# motherboard_2ch_arduino.net
KiCad netlist of a schematic drawn in Altium Designer
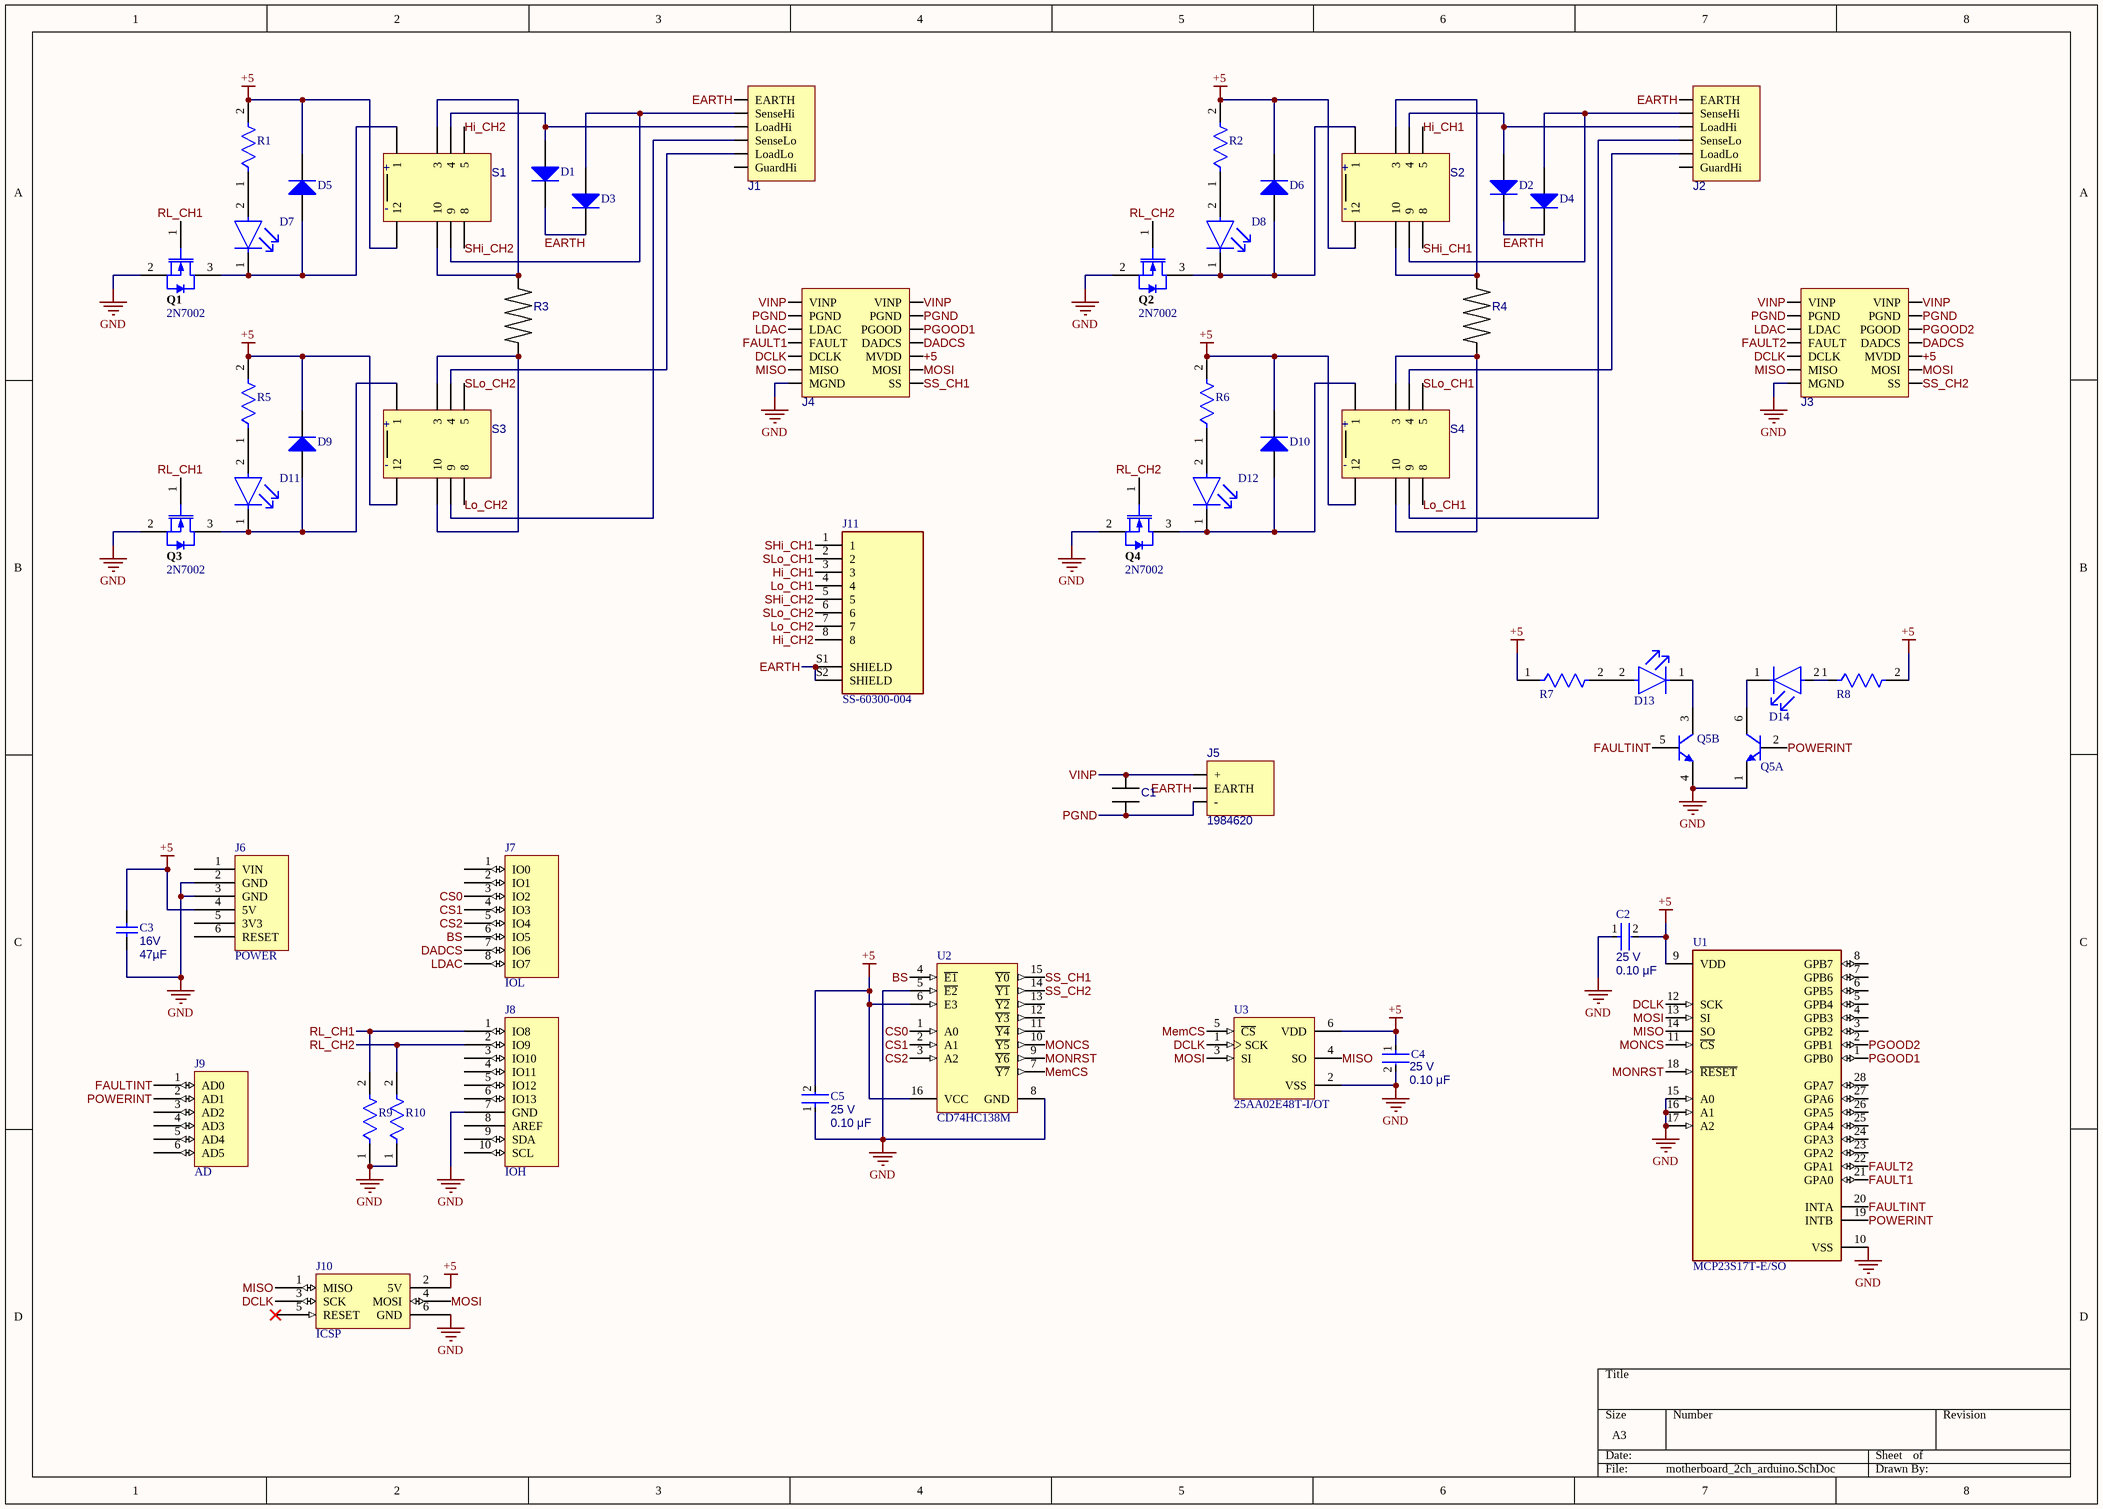
[diagram p0: motherboard_2ch_arduino.SchDoc]

(export (version "E")
  (design (tool "Eeschema 10.0.6"))
  (components
    (comp (ref "C1")
      (value "KRM55TR71H226MH01L")
      (footprint "CAPC6050X50M")
      (libsource (lib "manual") (part "CAP22uF"))
    )
    (comp (ref "C2")
      (value "0.10 μF")
      (footprint "FP-C1206C-EB-IPC_A")
      (description "CAP CER 0.1UF 25V C0G/NP0 1206")
      (fields
        (field (name "VOLTAGE RATING") "25 V")
        (field (name "MANUFACTURER") "KEMET")
        (field (name "TOLERANCE") "0.05")
      )
      (libsource (lib "Altium Content Vault") (part "b4654b650e69147ec39a6b967a45e02"))
    )
    (comp (ref "C3")
      (value "1210YD107MAT2A")
      (footprint "MURA-1210_H_2.7_M")
      (description "Cap Ceramic, 47 uF, +/- 10%, -55 to 85 degC, 2-Pin SMD (1210), RoHS, Tape and Reel")
      (fields
        (field (name "VOLTAGE RATING DC") "16V")
        (field (name "CAPACITANCE") "47µF")
        (field (name "TOLERANCE") "±10%")
        (field (name "MANUFACTURER") "Murata")
      )
      (libsource (lib "Altium Content Vault") (part "CAP-NP-2"))
    )
    (comp (ref "C4")
      (value "0.10 μF")
      (footprint "FP-C1206C-EB-IPC_A")
      (description "CAP CER 0.1UF 25V C0G/NP0 1206")
      (fields
        (field (name "VOLTAGE RATING") "25 V")
        (field (name "MANUFACTURER") "KEMET")
        (field (name "TOLERANCE") "0.05")
      )
      (libsource (lib "Altium Content Vault") (part "b4654b650e69147ec39a6b967a45e02"))
    )
    (comp (ref "C5")
      (value "0.10 μF")
      (footprint "FP-C1206C-EB-IPC_A")
      (description "CAP CER 0.1UF 25V C0G/NP0 1206")
      (fields
        (field (name "VOLTAGE RATING") "25 V")
        (field (name "MANUFACTURER") "KEMET")
        (field (name "TOLERANCE") "0.05")
      )
      (libsource (lib "Altium Content Vault") (part "b4654b650e69147ec39a6b967a45e02"))
    )
    (comp (ref "D1")
      (value "SMAJ33CA-TR")
      (footprint "STM-SMA-2_V")
      (description "Transil(TM) Diode, 33 A, 36.7 V, -55 to 150 degC, 2-Pin SMA, RoHS, Tape and Reel")
      (fields (field (name "MANUFACTURER") "STMicroelectronics"))
      (libsource (lib "Altium Content Vault") (part "D-AK-2"))
    )
    (comp (ref "D2")
      (value "SMAJ33CA-TR")
      (footprint "STM-SMA-2_V")
      (description "Transil(TM) Diode, 33 A, 36.7 V, -55 to 150 degC, 2-Pin SMA, RoHS, Tape and Reel")
      (fields (field (name "MANUFACTURER") "STMicroelectronics"))
      (libsource (lib "Altium Content Vault") (part "D-AK-2"))
    )
    (comp (ref "D3")
      (value "SMAJ33CA-TR")
      (footprint "STM-SMA-2_V")
      (description "Transil(TM) Diode, 33 A, 36.7 V, -55 to 150 degC, 2-Pin SMA, RoHS, Tape and Reel")
      (fields (field (name "MANUFACTURER") "STMicroelectronics"))
      (libsource (lib "Altium Content Vault") (part "D-AK-2"))
    )
    (comp (ref "D4")
      (value "SMAJ33CA-TR")
      (footprint "STM-SMA-2_V")
      (description "Transil(TM) Diode, 33 A, 36.7 V, -55 to 150 degC, 2-Pin SMA, RoHS, Tape and Reel")
      (fields (field (name "MANUFACTURER") "STMicroelectronics"))
      (libsource (lib "Altium Content Vault") (part "D-AK-2"))
    )
    (comp (ref "D5")
      (value "1N4148W-7-F")
      (footprint "DIOD-SOD123-2_V")
      (description "Fast Switching Diode, 100 V, 0.15 A, -65 to 150 degC, 2-Pin?SOD123, RoHS, Tape and Reel")
      (fields (field (name "MANUFACTURER") "DiodesIncorporated"))
      (libsource (lib "Altium Content Vault") (part "D-AK-2"))
    )
    (comp (ref "D6")
      (value "1N4148W-7-F")
      (footprint "DIOD-SOD123-2_V")
      (description "Fast Switching Diode, 100 V, 0.15 A, -65 to 150 degC, 2-Pin?SOD123, RoHS, Tape and Reel")
      (fields (field (name "MANUFACTURER") "DiodesIncorporated"))
      (libsource (lib "Altium Content Vault") (part "D-AK-2"))
    )
    (comp (ref "D7")
      (value "LTST-C150KGKT")
      (footprint "FP-LTST-C150KGKT-MFG")
      (description "LED GREEN CLEAR 1206 SMD")
      (libsource (lib "Altium Content Vault") (part "8706943c75ba83719d021d2fdc84c58"))
    )
    (comp (ref "D8")
      (value "LTST-C150KGKT")
      (footprint "FP-LTST-C150KGKT-MFG")
      (description "LED GREEN CLEAR 1206 SMD")
      (libsource (lib "Altium Content Vault") (part "8706943c75ba83719d021d2fdc84c58"))
    )
    (comp (ref "D9")
      (value "1N4148W-7-F")
      (footprint "DIOD-SOD123-2_V")
      (description "Fast Switching Diode, 100 V, 0.15 A, -65 to 150 degC, 2-Pin?SOD123, RoHS, Tape and Reel")
      (fields (field (name "MANUFACTURER") "DiodesIncorporated"))
      (libsource (lib "Altium Content Vault") (part "D-AK-2"))
    )
    (comp (ref "D10")
      (value "1N4148W-7-F")
      (footprint "DIOD-SOD123-2_V")
      (description "Fast Switching Diode, 100 V, 0.15 A, -65 to 150 degC, 2-Pin?SOD123, RoHS, Tape and Reel")
      (fields (field (name "MANUFACTURER") "DiodesIncorporated"))
      (libsource (lib "Altium Content Vault") (part "D-AK-2"))
    )
    (comp (ref "D11")
      (value "LTST-C150KGKT")
      (footprint "FP-LTST-C150KGKT-MFG")
      (description "LED GREEN CLEAR 1206 SMD")
      (libsource (lib "Altium Content Vault") (part "8706943c75ba83719d021d2fdc84c58"))
    )
    (comp (ref "D12")
      (value "LTST-C150KGKT")
      (footprint "FP-LTST-C150KGKT-MFG")
      (description "LED GREEN CLEAR 1206 SMD")
      (libsource (lib "Altium Content Vault") (part "8706943c75ba83719d021d2fdc84c58"))
    )
    (comp (ref "D13")
      (value "LTST-C150KGKT")
      (footprint "FP-LTST-C150KGKT-MFG")
      (description "LED GREEN CLEAR 1206 SMD")
      (libsource (lib "Altium Content Vault") (part "8706943c75ba83719d021d2fdc84c58"))
    )
    (comp (ref "D14")
      (value "LTST-C150KGKT")
      (footprint "FP-LTST-C150KGKT-MFG")
      (description "LED GREEN CLEAR 1206 SMD")
      (libsource (lib "Altium Content Vault") (part "8706943c75ba83719d021d2fdc84c58"))
    )
    (comp (ref "J1") (value "5-146276-6") (footprint "SMUIO") (libsource (lib "manual") (part "SMUIO")))
    (comp (ref "J2") (value "5-146276-6") (footprint "SMUIO") (libsource (lib "manual") (part "SMUIO")))
    (comp (ref "J3") (value "5-146252-7") (footprint "DATAIO") (libsource (lib "manual") (part "DATAIO")))
    (comp (ref "J4") (value "5-146252-7") (footprint "DATAIO") (libsource (lib "manual") (part "DATAIO")))
    (comp (ref "J5") (value "1984620") (footprint "1984620") (libsource (lib "manual") (part "POWERJACK")))
    (comp (ref "J6") (value "POWER") (footprint "Header 6x1 8.5mm") (libsource (lib "Header") (part "POWER")))
    (comp (ref "J7") (value "IOL") (footprint "Header 8x1 8.5mm") (libsource (lib "Header") (part "IOL")))
    (comp (ref "J8") (value "IOH") (footprint "Header 10x1 8.5mm") (libsource (lib "Header") (part "IOH")))
    (comp (ref "J9")
      (value "AD")
      (footprint "Header:Header 6x1 8.5mm")
      (libsource (lib "Header") (part "AD"))
    )
    (comp (ref "J10") (value "ICSP") (footprint "ICSP") (libsource (lib "Header") (part "ICSP")))
    (comp (ref "J11")
      (value "SS-60300-004")
      (footprint "BEL_SS-60300-004")
      (description "Modular Jack ¦ CAT6a ¦ Horizontal (90) ¦ 8P 8C ¦ NF Shielded")
      (fields (field (name "MF") "Stewart Connector"))
      (libsource (lib "SS-60300-004") (part "SS-60300-004"))
    )
    (comp (ref "Q1")
      (value "2N7002")
      (footprint "INF-PG-SOT23_M")
      (fields (field (name "MANUFACTURER") "Infineon"))
      (libsource (lib "Altium Content Vault") (part "INF-NDMOS-GSD-3"))
    )
    (comp (ref "Q2")
      (value "2N7002")
      (footprint "INF-PG-SOT23_M")
      (fields (field (name "MANUFACTURER") "Infineon"))
      (libsource (lib "Altium Content Vault") (part "INF-NDMOS-GSD-3"))
    )
    (comp (ref "Q3")
      (value "2N7002")
      (footprint "INF-PG-SOT23_M")
      (fields (field (name "MANUFACTURER") "Infineon"))
      (libsource (lib "Altium Content Vault") (part "INF-NDMOS-GSD-3"))
    )
    (comp (ref "Q4")
      (value "2N7002")
      (footprint "INF-PG-SOT23_M")
      (fields (field (name "MANUFACTURER") "Infineon"))
      (libsource (lib "Altium Content Vault") (part "INF-NDMOS-GSD-3"))
    )
    (comp (ref "Q5")
      (value "MBT3904DW1T1G")
      (footprint "ONSC-SOT-363-6-419B-02_W_V")
      (description "Dual General Purpose Transistors, 6-Pin SOT-363, Pb-Free, Tape and Reel")
      (fields (field (name "MANUFACTURER") "On Semiconductor"))
      (libsource (lib "Altium Content Vault") (part "ONSC-NPN_NPN-6_F"))
    )
    (comp (ref "R1")
      (value "RN73R2BTTD1001B25")
      (footprint "FP-RC3216-IPC_A")
      (description "Res Thick Film 1206 1kΩ 5% 0.25W ±100ppm/°C Molded SMD T/R")
      (fields (field (name "TOLERANCE") "5%"))
      (libsource (lib "Altium Content Vault") (part "1029c3af85768c4190bb7ad29bc67b5"))
    )
    (comp (ref "R2")
      (value "RC3216J102CS")
      (footprint "FP-RC3216-IPC_A")
      (description "Res Thick Film 1206 1kΩ 5% 0.25W ±100ppm/°C Molded SMD T/R")
      (fields (field (name "TOLERANCE") "5%"))
      (libsource (lib "Altium Content Vault") (part "1029c3af85768c4190bb7ad29bc67b5"))
    )
    (comp (ref "R3")
      (value "Y1453500R000V9L")
      (footprint "Y1453500R000V9L")
      (libsource (lib "manual") (part "Y1453500R000V9L"))
    )
    (comp (ref "R4")
      (value "Y1453500R000V9L")
      (footprint "Y1453500R000V9L")
      (libsource (lib "manual") (part "Y1453500R000V9L"))
    )
    (comp (ref "R5")
      (value "RC3216J102CS")
      (footprint "FP-RC3216-IPC_A")
      (description "Res Thick Film 1206 1kΩ 5% 0.25W ±100ppm/°C Molded SMD T/R")
      (fields (field (name "TOLERANCE") "5%"))
      (libsource (lib "Altium Content Vault") (part "1029c3af85768c4190bb7ad29bc67b5"))
    )
    (comp (ref "R6")
      (value "RC3216J102CS")
      (footprint "FP-RC3216-IPC_A")
      (description "Res Thick Film 1206 1kΩ 5% 0.25W ±100ppm/°C Molded SMD T/R")
      (fields (field (name "TOLERANCE") "5%"))
      (libsource (lib "Altium Content Vault") (part "1029c3af85768c4190bb7ad29bc67b5"))
    )
    (comp (ref "R7")
      (value "RC3216J102CS")
      (footprint "FP-RC3216-IPC_A")
      (description "Res Thick Film 1206 1kΩ 5% 0.25W ±100ppm/°C Molded SMD T/R")
      (fields (field (name "TOLERANCE") "5%"))
      (libsource (lib "Altium Content Vault") (part "1029c3af85768c4190bb7ad29bc67b5"))
    )
    (comp (ref "R8")
      (value "RC3216J102CS")
      (footprint "FP-RC3216-IPC_A")
      (description "Res Thick Film 1206 1kΩ 5% 0.25W ±100ppm/°C Molded SMD T/R")
      (fields (field (name "TOLERANCE") "5%"))
      (libsource (lib "Altium Content Vault") (part "1029c3af85768c4190bb7ad29bc67b5"))
    )
    (comp (ref "R9")
      (value "RN73H2BTTD1002B10")
      (footprint "FP-RC3216-IPC_A")
      (description "RES SMD 10K OHM 1% 1/4W 1206")
      (fields (field (name "TOLERANCE") "1%"))
      (libsource (lib "Altium Content Vault") (part "1029c3af85768c4190bb7ad29bc67b5"))
    )
    (comp (ref "R10")
      (value "RN73H2BTTD1002B10")
      (footprint "FP-RC3216-IPC_A")
      (description "RES SMD 10K OHM 1% 1/4W 1206")
      (fields (field (name "TOLERANCE") "1%"))
      (libsource (lib "Altium Content Vault") (part "1029c3af85768c4190bb7ad29bc67b5"))
    )
    (comp (ref "S1") (value "G6S-2 DC5") (footprint "EE2-5NU") (libsource (lib "manual") (part "EE2-5NU")))
    (comp (ref "S2") (value "G6S-2 DC5") (footprint "EE2-5NU") (libsource (lib "manual") (part "EE2-5NU")))
    (comp (ref "S3") (value "G6S-2 DC5") (footprint "EE2-5NU") (libsource (lib "manual") (part "EE2-5NU")))
    (comp (ref "S4") (value "G6S-2 DC5") (footprint "EE2-5NU") (libsource (lib "manual") (part "EE2-5NU")))
    (comp (ref "U1")
      (value "MCP23S17T-E/SO")
      (footprint "FP-C04-052-MFG")
      (description "IC I/O EXPANDER SPI 16B 28SOIC")
      (libsource (lib "Altium Content Vault") (part "be0e9b41ae9def86c3880ffea09bd70"))
    )
    (comp (ref "U2")
      (value "CD74HC138M")
      (footprint "D0016A_M")
      (description "High Speed CMOS Logic 3-to-8 Line Decoder Demultiplexer Inverting and Non-Inverting, D0016A, TUBE")
      (fields
        (field (name "MANUFACTURER") "Texas Instruments")
        (field (name "GENERIC PART NUMBER") "CD74HC138")
      )
      (libsource (lib "Altium Content Vault") (part "TI-CDX4HCT138-16"))
    )
    (comp (ref "U3")
      (value "25AA02E48T-I/OT")
      (footprint "SOT-23-OT6_M")
      (libsource (lib "Altium Content Vault") (part "MEM-SEEPROM-25XX0X0A-6"))
    )
  )
  (nets
    (net (code "1") (name "+5") (class "Default")
      (node (ref "C2") (pin "2") (pinfunction "2_2") (pintype "passive"))
      (node (ref "C3") (pin "2") (pinfunction "2_2") (pintype "passive"))
      (node (ref "C4") (pin "1") (pinfunction "1_1") (pintype "passive"))
      (node (ref "C5") (pin "2") (pinfunction "2_2") (pintype "passive"))
      (node (ref "D10") (pin "2") (pinfunction "K_2") (pintype "passive"))
      (node (ref "D5") (pin "2") (pinfunction "K_2") (pintype "passive"))
      (node (ref "D6") (pin "2") (pinfunction "K_2") (pintype "passive"))
      (node (ref "D9") (pin "2") (pinfunction "K_2") (pintype "passive"))
      (node (ref "J10") (pin "2") (pinfunction "5V_2") (pintype "power_in"))
      (node (ref "J3") (pin "10") (pinfunction "MVDD_10") (pintype "passive"))
      (node (ref "J4") (pin "10") (pinfunction "MVDD_10") (pintype "passive"))
      (node (ref "J6") (pin "4") (pinfunction "5V_4") (pintype "power_in"))
      (node (ref "R1") (pin "2") (pinfunction "2_2") (pintype "passive"))
      (node (ref "R2") (pin "2") (pinfunction "2_2") (pintype "passive"))
      (node (ref "R5") (pin "2") (pinfunction "2_2") (pintype "passive"))
      (node (ref "R6") (pin "2") (pinfunction "2_2") (pintype "passive"))
      (node (ref "R7") (pin "1") (pinfunction "1_1") (pintype "passive"))
      (node (ref "R8") (pin "2") (pinfunction "2_2") (pintype "passive"))
      (node (ref "S1") (pin "12") (pinfunction "12_12") (pintype "passive"))
      (node (ref "S2") (pin "12") (pinfunction "12_12") (pintype "passive"))
      (node (ref "S3") (pin "12") (pinfunction "12_12") (pintype "passive"))
      (node (ref "S4") (pin "12") (pinfunction "12_12") (pintype "passive"))
      (node (ref "U1") (pin "9") (pinfunction "VDD_9") (pintype "power_in"))
      (node (ref "U2") (pin "16") (pinfunction "VCC_16") (pintype "power_in"))
      (node (ref "U2") (pin "6") (pinfunction "E3_6") (pintype "input"))
      (node (ref "U3") (pin "6") (pinfunction "VDD_6") (pintype "power_in"))
    )
    (net (code "2") (name "/BS") (class "Default")
      (node (ref "J7") (pin "6") (pinfunction "IO5_6") (pintype "bidirectional"))
      (node (ref "U2") (pin "4") (pinfunction "~{E1}_4") (pintype "input"))
    )
    (net (code "3") (name "/CS0") (class "Default")
      (node (ref "J7") (pin "3") (pinfunction "IO2_3") (pintype "bidirectional"))
      (node (ref "U2") (pin "1") (pinfunction "A0_1") (pintype "input"))
    )
    (net (code "4") (name "/CS1") (class "Default")
      (node (ref "J7") (pin "4") (pinfunction "IO3_4") (pintype "bidirectional"))
      (node (ref "U2") (pin "2") (pinfunction "A1_2") (pintype "input"))
    )
    (net (code "5") (name "/CS2") (class "Default")
      (node (ref "J7") (pin "5") (pinfunction "IO4_5") (pintype "bidirectional"))
      (node (ref "U2") (pin "3") (pinfunction "A2_3") (pintype "input"))
    )
    (net (code "6") (name "/DADCS") (class "Default")
      (node (ref "J3") (pin "8") (pinfunction "DADCS_8") (pintype "passive"))
      (node (ref "J4") (pin "8") (pinfunction "DADCS_8") (pintype "passive"))
      (node (ref "J7") (pin "7") (pinfunction "IO6_7") (pintype "bidirectional"))
    )
    (net (code "7") (name "/DCLK") (class "Default")
      (node (ref "J10") (pin "3") (pinfunction "SCK_3") (pintype "bidirectional"))
      (node (ref "J3") (pin "9") (pinfunction "DCLK_9") (pintype "passive"))
      (node (ref "J4") (pin "9") (pinfunction "DCLK_9") (pintype "passive"))
      (node (ref "U1") (pin "12") (pinfunction "SCK_12") (pintype "input"))
      (node (ref "U3") (pin "1") (pinfunction "SCK_1") (pintype "input"))
    )
    (net (code "8") (name "/EARTH") (class "Default")
      (node (ref "D1") (pin "2") (pinfunction "K_2") (pintype "passive"))
      (node (ref "D2") (pin "2") (pinfunction "K_2") (pintype "passive"))
      (node (ref "D3") (pin "2") (pinfunction "K_2") (pintype "passive"))
      (node (ref "D4") (pin "2") (pinfunction "K_2") (pintype "passive"))
      (node (ref "J1") (pin "1") (pinfunction "EARTH_1") (pintype "passive"))
      (node (ref "J11") (pin "S1") (pinfunction "SHIELD_S1") (pintype "passive"))
      (node (ref "J11") (pin "S2") (pinfunction "SHIELD_S2") (pintype "passive"))
      (node (ref "J2") (pin "1") (pinfunction "EARTH_1") (pintype "passive"))
      (node (ref "J5") (pin "2") (pinfunction "EARTH_2") (pintype "passive"))
    )
    (net (code "9") (name "/FAULT1") (class "Default")
      (node (ref "J4") (pin "7") (pinfunction "FAULT_7") (pintype "passive"))
      (node (ref "U1") (pin "21") (pinfunction "GPA0_21") (pintype "bidirectional"))
    )
    (net (code "10") (name "/FAULT2") (class "Default")
      (node (ref "J3") (pin "7") (pinfunction "FAULT_7") (pintype "passive"))
      (node (ref "U1") (pin "22") (pinfunction "GPA1_22") (pintype "bidirectional"))
    )
    (net (code "11") (name "/FAULTINT") (class "Default")
      (node (ref "J9") (pin "1") (pinfunction "AD0_1") (pintype "bidirectional"))
      (node (ref "Q5") (pin "5") (pinfunction "B_5") (pintype "passive"))
      (node (ref "U1") (pin "20") (pinfunction "INTA_20") (pintype "open_collector"))
    )
    (net (code "12") (name "/Hi_CH1") (class "Default")
      (node (ref "J11") (pin "3") (pinfunction "3_3") (pintype "passive"))
      (node (ref "S2") (pin "5") (pinfunction "5_5") (pintype "passive"))
    )
    (net (code "13") (name "/Hi_CH2") (class "Default")
      (node (ref "J11") (pin "8") (pinfunction "8_8") (pintype "passive"))
      (node (ref "S1") (pin "5") (pinfunction "5_5") (pintype "passive"))
    )
    (net (code "14") (name "/LDAC") (class "Default")
      (node (ref "J3") (pin "5") (pinfunction "LDAC_5") (pintype "passive"))
      (node (ref "J4") (pin "5") (pinfunction "LDAC_5") (pintype "passive"))
      (node (ref "J7") (pin "8") (pinfunction "IO7_8") (pintype "bidirectional"))
    )
    (net (code "15") (name "/Lo_CH1") (class "Default")
      (node (ref "J11") (pin "4") (pinfunction "4_4") (pintype "passive"))
      (node (ref "S4") (pin "8") (pinfunction "8_8") (pintype "passive"))
    )
    (net (code "16") (name "/Lo_CH2") (class "Default")
      (node (ref "J11") (pin "7") (pinfunction "7_7") (pintype "passive"))
      (node (ref "S3") (pin "8") (pinfunction "8_8") (pintype "passive"))
    )
    (net (code "17") (name "/MISO") (class "Default")
      (node (ref "J10") (pin "1") (pinfunction "MISO_1") (pintype "bidirectional"))
      (node (ref "J3") (pin "11") (pinfunction "MISO_11") (pintype "passive"))
      (node (ref "J4") (pin "11") (pinfunction "MISO_11") (pintype "passive"))
      (node (ref "U1") (pin "14") (pinfunction "SO_14") (pintype "tri_state"))
      (node (ref "U3") (pin "4") (pinfunction "SO_4") (pintype "tri_state"))
    )
    (net (code "18") (name "/MONCS") (class "Default")
      (node (ref "U1") (pin "11") (pinfunction "~{CS}_11") (pintype "input"))
      (node (ref "U2") (pin "10") (pinfunction "~{Y5}_10") (pintype "output"))
    )
    (net (code "19") (name "/MONRST") (class "Default")
      (node (ref "U1") (pin "18") (pinfunction "~{RESET}_18") (pintype "input"))
      (node (ref "U2") (pin "9") (pinfunction "~{Y6}_9") (pintype "output"))
    )
    (net (code "20") (name "/MOSI") (class "Default")
      (node (ref "J10") (pin "4") (pinfunction "MOSI_4") (pintype "bidirectional"))
      (node (ref "J3") (pin "12") (pinfunction "MOSI_12") (pintype "passive"))
      (node (ref "J4") (pin "12") (pinfunction "MOSI_12") (pintype "passive"))
      (node (ref "U1") (pin "13") (pinfunction "SI_13") (pintype "input"))
      (node (ref "U3") (pin "3") (pinfunction "SI_3") (pintype "input"))
    )
    (net (code "21") (name "/MemCS") (class "Default")
      (node (ref "U2") (pin "7") (pinfunction "~{Y7}_7") (pintype "output"))
      (node (ref "U3") (pin "5") (pinfunction "~{CS}_5") (pintype "input"))
    )
    (net (code "22") (name "/PGND") (class "Default")
      (node (ref "C1") (pin "1") (pintype "passive"))
      (node (ref "J3") (pin "3") (pinfunction "PGND_3") (pintype "passive"))
      (node (ref "J3") (pin "4") (pinfunction "PGND_4") (pintype "passive"))
      (node (ref "J4") (pin "3") (pinfunction "PGND_3") (pintype "passive"))
      (node (ref "J4") (pin "4") (pinfunction "PGND_4") (pintype "passive"))
      (node (ref "J5") (pin "3") (pinfunction "-_3") (pintype "passive"))
    )
    (net (code "23") (name "/PGOOD1") (class "Default")
      (node (ref "J4") (pin "6") (pinfunction "PGOOD_6") (pintype "passive"))
      (node (ref "U1") (pin "1") (pinfunction "GPB0_1") (pintype "bidirectional"))
    )
    (net (code "24") (name "/PGOOD2") (class "Default")
      (node (ref "J3") (pin "6") (pinfunction "PGOOD_6") (pintype "passive"))
      (node (ref "U1") (pin "2") (pinfunction "GPB1_2") (pintype "bidirectional"))
    )
    (net (code "25") (name "/POWERINT") (class "Default")
      (node (ref "J9") (pin "2") (pinfunction "AD1_2") (pintype "bidirectional"))
      (node (ref "Q5") (pin "2") (pinfunction "B_2") (pintype "passive"))
      (node (ref "U1") (pin "19") (pinfunction "INTB_19") (pintype "open_collector"))
    )
    (net (code "26") (name "/RL_CH1") (class "Default")
      (node (ref "J8") (pin "1") (pinfunction "IO8_1") (pintype "bidirectional"))
      (node (ref "Q1") (pin "1") (pinfunction "GATE_1") (pintype "passive"))
      (node (ref "Q3") (pin "1") (pinfunction "GATE_1") (pintype "passive"))
      (node (ref "R9") (pin "2") (pinfunction "2_2") (pintype "passive"))
    )
    (net (code "27") (name "/RL_CH2") (class "Default")
      (node (ref "J8") (pin "2") (pinfunction "IO9_2") (pintype "bidirectional"))
      (node (ref "Q2") (pin "1") (pinfunction "GATE_1") (pintype "passive"))
      (node (ref "Q4") (pin "1") (pinfunction "GATE_1") (pintype "passive"))
      (node (ref "R10") (pin "2") (pinfunction "2_2") (pintype "passive"))
    )
    (net (code "28") (name "/SHi_CH1") (class "Default")
      (node (ref "J11") (pin "1") (pinfunction "1_1") (pintype "passive"))
      (node (ref "S2") (pin "8") (pinfunction "8_8") (pintype "passive"))
    )
    (net (code "29") (name "/SHi_CH2") (class "Default")
      (node (ref "J11") (pin "5") (pinfunction "5_5") (pintype "passive"))
      (node (ref "S1") (pin "8") (pinfunction "8_8") (pintype "passive"))
    )
    (net (code "30") (name "/SLo_CH1") (class "Default")
      (node (ref "J11") (pin "2") (pinfunction "2_2") (pintype "passive"))
      (node (ref "S4") (pin "5") (pinfunction "5_5") (pintype "passive"))
    )
    (net (code "31") (name "/SLo_CH2") (class "Default")
      (node (ref "J11") (pin "6") (pinfunction "6_6") (pintype "passive"))
      (node (ref "S3") (pin "5") (pinfunction "5_5") (pintype "passive"))
    )
    (net (code "32") (name "/SS_CH1") (class "Default")
      (node (ref "J4") (pin "14") (pinfunction "SS_14") (pintype "passive"))
      (node (ref "U2") (pin "15") (pinfunction "~{Y0}_15") (pintype "output"))
    )
    (net (code "33") (name "/SS_CH2") (class "Default")
      (node (ref "J3") (pin "14") (pinfunction "SS_14") (pintype "passive"))
      (node (ref "U2") (pin "14") (pinfunction "~{Y1}_14") (pintype "output"))
    )
    (net (code "34") (name "/VINP") (class "Default")
      (node (ref "C1") (pin "2") (pintype "passive"))
      (node (ref "J3") (pin "1") (pinfunction "VINP_1") (pintype "passive"))
      (node (ref "J3") (pin "2") (pinfunction "VINP_2") (pintype "passive"))
      (node (ref "J4") (pin "1") (pinfunction "VINP_1") (pintype "passive"))
      (node (ref "J4") (pin "2") (pinfunction "VINP_2") (pintype "passive"))
      (node (ref "J5") (pin "1") (pinfunction "+_1") (pintype "passive"))
    )
    (net (code "35") (name "GND") (class "Default")
      (node (ref "C2") (pin "1") (pinfunction "1_1") (pintype "passive"))
      (node (ref "C3") (pin "1") (pinfunction "1_1") (pintype "passive"))
      (node (ref "C4") (pin "2") (pinfunction "2_2") (pintype "passive"))
      (node (ref "C5") (pin "1") (pinfunction "1_1") (pintype "passive"))
      (node (ref "J10") (pin "6") (pinfunction "GND_6") (pintype "power_in"))
      (node (ref "J3") (pin "13") (pinfunction "MGND_13") (pintype "passive"))
      (node (ref "J4") (pin "13") (pinfunction "MGND_13") (pintype "passive"))
      (node (ref "J6") (pin "2") (pinfunction "GND_2") (pintype "power_in"))
      (node (ref "J6") (pin "3") (pinfunction "GND_3") (pintype "power_in"))
      (node (ref "J8") (pin "7") (pinfunction "GND_7") (pintype "power_in"))
      (node (ref "Q1") (pin "2") (pinfunction "SOURCE_2") (pintype "passive"))
      (node (ref "Q2") (pin "2") (pinfunction "SOURCE_2") (pintype "passive"))
      (node (ref "Q3") (pin "2") (pinfunction "SOURCE_2") (pintype "passive"))
      (node (ref "Q4") (pin "2") (pinfunction "SOURCE_2") (pintype "passive"))
      (node (ref "Q5") (pin "1") (pinfunction "E_1") (pintype "passive"))
      (node (ref "Q5") (pin "4") (pinfunction "E_4") (pintype "passive"))
      (node (ref "R10") (pin "1") (pinfunction "1_1") (pintype "passive"))
      (node (ref "R9") (pin "1") (pinfunction "1_1") (pintype "passive"))
      (node (ref "U1") (pin "10") (pinfunction "VSS_10") (pintype "power_in"))
      (node (ref "U1") (pin "15") (pinfunction "A0_15") (pintype "input"))
      (node (ref "U1") (pin "16") (pinfunction "A1_16") (pintype "input"))
      (node (ref "U1") (pin "17") (pinfunction "A2_17") (pintype "input"))
      (node (ref "U2") (pin "5") (pinfunction "~{E2}_5") (pintype "input"))
      (node (ref "U2") (pin "8") (pinfunction "GND_8") (pintype "power_in"))
      (node (ref "U3") (pin "2") (pinfunction "VSS_2") (pintype "power_in"))
    )
    (net (code "36") (name "Net-(D1-A)") (class "Default")
      (node (ref "D1") (pin "1") (pinfunction "A_1") (pintype "passive"))
      (node (ref "J1") (pin "3") (pinfunction "LoadHi_3") (pintype "passive"))
      (node (ref "S1") (pin "4") (pinfunction "4_4") (pintype "passive"))
    )
    (net (code "37") (name "Net-(D2-A)") (class "Default")
      (node (ref "D2") (pin "1") (pinfunction "A_1") (pintype "passive"))
      (node (ref "J2") (pin "3") (pinfunction "LoadHi_3") (pintype "passive"))
      (node (ref "S2") (pin "4") (pinfunction "4_4") (pintype "passive"))
    )
    (net (code "38") (name "Net-(D3-A)") (class "Default")
      (node (ref "D3") (pin "1") (pinfunction "A_1") (pintype "passive"))
      (node (ref "J1") (pin "2") (pinfunction "SenseHi_2") (pintype "passive"))
      (node (ref "S1") (pin "9") (pinfunction "9_9") (pintype "passive"))
    )
    (net (code "39") (name "Net-(D4-A)") (class "Default")
      (node (ref "D4") (pin "1") (pinfunction "A_1") (pintype "passive"))
      (node (ref "J2") (pin "2") (pinfunction "SenseHi_2") (pintype "passive"))
      (node (ref "S2") (pin "9") (pinfunction "9_9") (pintype "passive"))
    )
    (net (code "40") (name "Net-(D5-A)") (class "Default")
      (node (ref "D5") (pin "1") (pinfunction "A_1") (pintype "passive"))
      (node (ref "D7") (pin "1") (pinfunction "C_1") (pintype "passive"))
      (node (ref "Q1") (pin "3") (pinfunction "DRAIN_3") (pintype "passive"))
      (node (ref "S1") (pin "1") (pinfunction "1_1") (pintype "passive"))
    )
    (net (code "41") (name "Net-(D6-A)") (class "Default")
      (node (ref "D6") (pin "1") (pinfunction "A_1") (pintype "passive"))
      (node (ref "D8") (pin "1") (pinfunction "C_1") (pintype "passive"))
      (node (ref "Q2") (pin "3") (pinfunction "DRAIN_3") (pintype "passive"))
      (node (ref "S2") (pin "1") (pinfunction "1_1") (pintype "passive"))
    )
    (net (code "42") (name "Net-(D7-A)") (class "Default")
      (node (ref "D7") (pin "2") (pinfunction "A_2") (pintype "passive"))
      (node (ref "R1") (pin "1") (pinfunction "1_1") (pintype "passive"))
    )
    (net (code "43") (name "Net-(D8-A)") (class "Default")
      (node (ref "D8") (pin "2") (pinfunction "A_2") (pintype "passive"))
      (node (ref "R2") (pin "1") (pinfunction "1_1") (pintype "passive"))
    )
    (net (code "44") (name "Net-(D10-A)") (class "Default")
      (node (ref "D10") (pin "1") (pinfunction "A_1") (pintype "passive"))
      (node (ref "D12") (pin "1") (pinfunction "C_1") (pintype "passive"))
      (node (ref "Q4") (pin "3") (pinfunction "DRAIN_3") (pintype "passive"))
      (node (ref "S4") (pin "1") (pinfunction "1_1") (pintype "passive"))
    )
    (net (code "45") (name "Net-(D11-A)") (class "Default")
      (node (ref "D11") (pin "2") (pinfunction "A_2") (pintype "passive"))
      (node (ref "R5") (pin "1") (pinfunction "1_1") (pintype "passive"))
    )
    (net (code "46") (name "Net-(D11-C)") (class "Default")
      (node (ref "D11") (pin "1") (pinfunction "C_1") (pintype "passive"))
      (node (ref "D9") (pin "1") (pinfunction "A_1") (pintype "passive"))
      (node (ref "Q3") (pin "3") (pinfunction "DRAIN_3") (pintype "passive"))
      (node (ref "S3") (pin "1") (pinfunction "1_1") (pintype "passive"))
    )
    (net (code "47") (name "Net-(D12-A)") (class "Default")
      (node (ref "D12") (pin "2") (pinfunction "A_2") (pintype "passive"))
      (node (ref "R6") (pin "1") (pinfunction "1_1") (pintype "passive"))
    )
    (net (code "48") (name "Net-(D13-A)") (class "Default")
      (node (ref "D13") (pin "2") (pinfunction "A_2") (pintype "passive"))
      (node (ref "R7") (pin "2") (pinfunction "2_2") (pintype "passive"))
    )
    (net (code "49") (name "Net-(D13-C)") (class "Default")
      (node (ref "D13") (pin "1") (pinfunction "C_1") (pintype "passive"))
      (node (ref "Q5") (pin "3") (pinfunction "C_3") (pintype "passive"))
    )
    (net (code "50") (name "Net-(D14-A)") (class "Default")
      (node (ref "D14") (pin "2") (pinfunction "A_2") (pintype "passive"))
      (node (ref "R8") (pin "1") (pinfunction "1_1") (pintype "passive"))
    )
    (net (code "51") (name "Net-(D14-C)") (class "Default")
      (node (ref "D14") (pin "1") (pinfunction "C_1") (pintype "passive"))
      (node (ref "Q5") (pin "6") (pinfunction "C_6") (pintype "passive"))
    )
    (net (code "52") (name "Net-(J1-LoadLo)") (class "Default")
      (node (ref "J1") (pin "5") (pinfunction "LoadLo_5") (pintype "passive"))
      (node (ref "S3") (pin "4") (pinfunction "4_4") (pintype "passive"))
    )
    (net (code "53") (name "Net-(J1-SenseLo)") (class "Default")
      (node (ref "J1") (pin "4") (pinfunction "SenseLo_4") (pintype "passive"))
      (node (ref "S3") (pin "9") (pinfunction "9_9") (pintype "passive"))
    )
    (net (code "54") (name "Net-(J2-LoadLo)") (class "Default")
      (node (ref "J2") (pin "5") (pinfunction "LoadLo_5") (pintype "passive"))
      (node (ref "S4") (pin "4") (pinfunction "4_4") (pintype "passive"))
    )
    (net (code "55") (name "Net-(J2-SenseLo)") (class "Default")
      (node (ref "J2") (pin "4") (pinfunction "SenseLo_4") (pintype "passive"))
      (node (ref "S4") (pin "9") (pinfunction "9_9") (pintype "passive"))
    )
    (net (code "56") (name "Net-(R3-Pad1)") (class "Default")
      (node (ref "R3") (pin "1") (pinfunction "1_1") (pintype "passive"))
      (node (ref "S3") (pin "10") (pinfunction "10_10") (pintype "passive"))
      (node (ref "S3") (pin "3") (pinfunction "3_3") (pintype "passive"))
    )
    (net (code "57") (name "Net-(R3-Pad2)") (class "Default")
      (node (ref "R3") (pin "2") (pinfunction "2_2") (pintype "passive"))
      (node (ref "S1") (pin "10") (pinfunction "10_10") (pintype "passive"))
      (node (ref "S1") (pin "3") (pinfunction "3_3") (pintype "passive"))
    )
    (net (code "58") (name "Net-(R4-Pad1)") (class "Default")
      (node (ref "R4") (pin "1") (pinfunction "1_1") (pintype "passive"))
      (node (ref "S4") (pin "10") (pinfunction "10_10") (pintype "passive"))
      (node (ref "S4") (pin "3") (pinfunction "3_3") (pintype "passive"))
    )
    (net (code "59") (name "Net-(R4-Pad2)") (class "Default")
      (node (ref "R4") (pin "2") (pinfunction "2_2") (pintype "passive"))
      (node (ref "S2") (pin "10") (pinfunction "10_10") (pintype "passive"))
      (node (ref "S2") (pin "3") (pinfunction "3_3") (pintype "passive"))
    )
    (net (code "60") (name "unconnected-(J1-GuardHi-Pad6)") (class "Default")
      (node (ref "J1") (pin "6") (pinfunction "GuardHi_6") (pintype "passive"))
    )
    (net (code "61") (name "unconnected-(J2-GuardHi-Pad6)") (class "Default")
      (node (ref "J2") (pin "6") (pinfunction "GuardHi_6") (pintype "passive"))
    )
    (net (code "62") (name "unconnected-(J6-3V3-Pad5)") (class "Default")
      (node (ref "J6") (pin "5") (pinfunction "3V3_5") (pintype "power_in"))
    )
    (net (code "63") (name "unconnected-(J6-RESET-Pad6)") (class "Default")
      (node (ref "J6") (pin "6") (pinfunction "RESET_6") (pintype "passive"))
    )
    (net (code "64") (name "unconnected-(J6-VIN-Pad1)") (class "Default")
      (node (ref "J6") (pin "1") (pinfunction "VIN_1") (pintype "power_in"))
    )
    (net (code "65") (name "unconnected-(J7-IO0-Pad1)") (class "Default")
      (node (ref "J7") (pin "1") (pinfunction "IO0_1") (pintype "bidirectional"))
    )
    (net (code "66") (name "unconnected-(J7-IO1-Pad2)") (class "Default")
      (node (ref "J7") (pin "2") (pinfunction "IO1_2") (pintype "bidirectional"))
    )
    (net (code "67") (name "unconnected-(J8-AREF-Pad8)") (class "Default")
      (node (ref "J8") (pin "8") (pinfunction "AREF_8") (pintype "passive"))
    )
    (net (code "68") (name "unconnected-(J8-IO10-Pad3)") (class "Default")
      (node (ref "J8") (pin "3") (pinfunction "IO10_3") (pintype "bidirectional"))
    )
    (net (code "69") (name "unconnected-(J8-IO11-Pad4)") (class "Default")
      (node (ref "J8") (pin "4") (pinfunction "IO11_4") (pintype "bidirectional"))
    )
    (net (code "70") (name "unconnected-(J8-IO12-Pad5)") (class "Default")
      (node (ref "J8") (pin "5") (pinfunction "IO12_5") (pintype "bidirectional"))
    )
    (net (code "71") (name "unconnected-(J8-IO13-Pad6)") (class "Default")
      (node (ref "J8") (pin "6") (pinfunction "IO13_6") (pintype "bidirectional"))
    )
    (net (code "72") (name "unconnected-(J8-SCL-Pad10)") (class "Default")
      (node (ref "J8") (pin "10") (pinfunction "SCL_10") (pintype "bidirectional"))
    )
    (net (code "73") (name "unconnected-(J8-SDA-Pad9)") (class "Default")
      (node (ref "J8") (pin "9") (pinfunction "SDA_9") (pintype "bidirectional"))
    )
    (net (code "74") (name "unconnected-(J9-AD2-Pad3)") (class "Default")
      (node (ref "J9") (pin "3") (pinfunction "AD2_3") (pintype "bidirectional"))
    )
    (net (code "75") (name "unconnected-(J9-AD3-Pad4)") (class "Default")
      (node (ref "J9") (pin "4") (pinfunction "AD3_4") (pintype "bidirectional"))
    )
    (net (code "76") (name "unconnected-(J9-AD4-Pad5)") (class "Default")
      (node (ref "J9") (pin "5") (pinfunction "AD4_5") (pintype "bidirectional"))
    )
    (net (code "77") (name "unconnected-(J9-AD5-Pad6)") (class "Default")
      (node (ref "J9") (pin "6") (pinfunction "AD5_6") (pintype "bidirectional"))
    )
    (net (code "78") (name "unconnected-(J10-RESET-Pad5)") (class "Default")
      (node (ref "J10") (pin "5") (pinfunction "RESET_5") (pintype "input+no_connect"))
    )
    (net (code "79") (name "unconnected-(U1-GPA2-Pad23)") (class "Default")
      (node (ref "U1") (pin "23") (pinfunction "GPA2_23") (pintype "bidirectional"))
    )
    (net (code "80") (name "unconnected-(U1-GPA3-Pad24)") (class "Default")
      (node (ref "U1") (pin "24") (pinfunction "GPA3_24") (pintype "bidirectional"))
    )
    (net (code "81") (name "unconnected-(U1-GPA4-Pad25)") (class "Default")
      (node (ref "U1") (pin "25") (pinfunction "GPA4_25") (pintype "bidirectional"))
    )
    (net (code "82") (name "unconnected-(U1-GPA5-Pad26)") (class "Default")
      (node (ref "U1") (pin "26") (pinfunction "GPA5_26") (pintype "bidirectional"))
    )
    (net (code "83") (name "unconnected-(U1-GPA6-Pad27)") (class "Default")
      (node (ref "U1") (pin "27") (pinfunction "GPA6_27") (pintype "bidirectional"))
    )
    (net (code "84") (name "unconnected-(U1-GPA7-Pad28)") (class "Default")
      (node (ref "U1") (pin "28") (pinfunction "GPA7_28") (pintype "bidirectional"))
    )
    (net (code "85") (name "unconnected-(U1-GPB2-Pad3)") (class "Default")
      (node (ref "U1") (pin "3") (pinfunction "GPB2_3") (pintype "bidirectional"))
    )
    (net (code "86") (name "unconnected-(U1-GPB3-Pad4)") (class "Default")
      (node (ref "U1") (pin "4") (pinfunction "GPB3_4") (pintype "bidirectional"))
    )
    (net (code "87") (name "unconnected-(U1-GPB4-Pad5)") (class "Default")
      (node (ref "U1") (pin "5") (pinfunction "GPB4_5") (pintype "bidirectional"))
    )
    (net (code "88") (name "unconnected-(U1-GPB5-Pad6)") (class "Default")
      (node (ref "U1") (pin "6") (pinfunction "GPB5_6") (pintype "bidirectional"))
    )
    (net (code "89") (name "unconnected-(U1-GPB6-Pad7)") (class "Default")
      (node (ref "U1") (pin "7") (pinfunction "GPB6_7") (pintype "bidirectional"))
    )
    (net (code "90") (name "unconnected-(U1-GPB7-Pad8)") (class "Default")
      (node (ref "U1") (pin "8") (pinfunction "GPB7_8") (pintype "bidirectional"))
    )
    (net (code "91") (name "unconnected-(U2-~{Y2}-Pad13)") (class "Default")
      (node (ref "U2") (pin "13") (pinfunction "~{Y2}_13") (pintype "output"))
    )
    (net (code "92") (name "unconnected-(U2-~{Y3}-Pad12)") (class "Default")
      (node (ref "U2") (pin "12") (pinfunction "~{Y3}_12") (pintype "output"))
    )
    (net (code "93") (name "unconnected-(U2-~{Y4}-Pad11)") (class "Default")
      (node (ref "U2") (pin "11") (pinfunction "~{Y4}_11") (pintype "output"))
    )
  )
)
